# SchematicOscillator.net
KiCad netlist of a schematic drawn in EAGLE
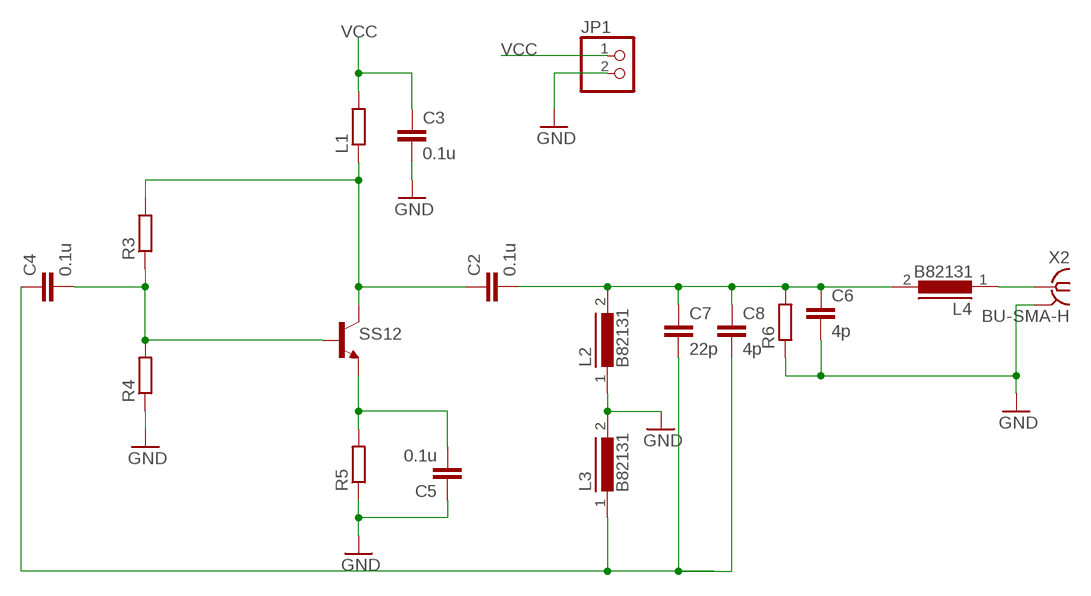
[diagram p0: schematic, sheet 1]

(export (version "E")
  (design (tool "Eeschema 10.0.6"))
  (components
    (comp (ref "C2")
      (value "0.1u")
      (footprint "eagle-import:C0805")
      (libsource (lib "eagle-import") (part "C-EUC0805"))
    )
    (comp (ref "C3")
      (value "0.1u")
      (footprint "eagle-import:C0805")
      (libsource (lib "eagle-import") (part "C-EUC0805"))
    )
    (comp (ref "C4")
      (value "0.1u")
      (footprint "eagle-import:C0805")
      (libsource (lib "eagle-import") (part "C-EUC0805"))
    )
    (comp (ref "C5")
      (value "0.1u")
      (footprint "eagle-import:C0805")
      (libsource (lib "eagle-import") (part "C-EUC0805"))
    )
    (comp (ref "C6")
      (value "4p")
      (footprint "eagle-import:C1206")
      (libsource (lib "eagle-import") (part "C-EUC1206"))
    )
    (comp (ref "C7")
      (value "22p")
      (footprint "eagle-import:C0805")
      (libsource (lib "eagle-import") (part "C-EUC0805"))
    )
    (comp (ref "C8")
      (value "4p")
      (footprint "eagle-import:C1206")
      (libsource (lib "eagle-import") (part "C-EUC1206"))
    )
    (comp (ref "JP1")
      (value "PINHD-1X2")
      (footprint "eagle-import:1X02")
      (libsource (lib "eagle-import") (part "PINHD-1X2"))
    )
    (comp (ref "L1")
      (value "R-EU_M0805")
      (footprint "eagle-import:M0805")
      (libsource (lib "eagle-import") (part "resistor_R-EU_M0805"))
    )
    (comp (ref "L2")
      (value "B82131")
      (footprint "eagle-import:SUKW1-17")
      (libsource (lib "eagle-import") (part "B82131"))
    )
    (comp (ref "L3")
      (value "B82131")
      (footprint "eagle-import:SUKW1-17")
      (libsource (lib "eagle-import") (part "B82131"))
    )
    (comp (ref "L4")
      (value "B82131")
      (footprint "eagle-import:SUKW1-17")
      (libsource (lib "eagle-import") (part "B82131"))
    )
    (comp (ref "R3")
      (value "R-EU_R1206")
      (footprint "eagle-import:R1206")
      (libsource (lib "eagle-import") (part "R-EU_R1206"))
    )
    (comp (ref "R4")
      (value "R-EU_R1206")
      (footprint "eagle-import:R1206")
      (libsource (lib "eagle-import") (part "R-EU_R1206"))
    )
    (comp (ref "R5")
      (value "R-EU_R1206")
      (footprint "eagle-import:R1206")
      (libsource (lib "eagle-import") (part "R-EU_R1206"))
    )
    (comp (ref "R6")
      (value "R-EU_R1206")
      (footprint "eagle-import:R1206")
      (libsource (lib "eagle-import") (part "R-EU_R1206"))
    )
    (comp (ref "SS12")
      (value "-NPN-TO92")
      (footprint "eagle-import:TO92")
      (libsource (lib "eagle-import") (part "-NPN-TO92"))
    )
    (comp (ref "X2")
      (value "BU-SMA-H")
      (footprint "eagle-import:BU-SMA-H")
      (libsource (lib "eagle-import") (part "BU-SMA-H"))
    )
  )
  (nets
    (net (code "1") (name "/VCC") (class "Default")
      (node (ref "C3") (pin "1") (pinfunction "1_1") (pintype "passive"))
      (node (ref "JP1") (pin "1") (pinfunction "1_1") (pintype "passive"))
      (node (ref "L1") (pin "2") (pinfunction "2_2") (pintype "passive"))
    )
    (net (code "2") (name "GND") (class "Default")
      (node (ref "C3") (pin "2") (pinfunction "2_2") (pintype "passive"))
      (node (ref "C5") (pin "1") (pinfunction "1_1") (pintype "passive"))
      (node (ref "C6") (pin "2") (pinfunction "2_2") (pintype "passive"))
      (node (ref "JP1") (pin "2") (pinfunction "2_2") (pintype "passive"))
      (node (ref "L2") (pin "1") (pinfunction "1_1") (pintype "passive"))
      (node (ref "L3") (pin "2") (pinfunction "2_2") (pintype "passive"))
      (node (ref "R4") (pin "1") (pinfunction "1_1") (pintype "passive"))
      (node (ref "R5") (pin "1") (pinfunction "1_1") (pintype "passive"))
      (node (ref "R6") (pin "1") (pinfunction "1_1") (pintype "passive"))
      (node (ref "X2") (pin "2") (pinfunction "2_2") (pintype "passive"))
      (node (ref "X2") (pin "3") (pinfunction "2_3") (pintype "passive"))
      (node (ref "X2") (pin "4") (pinfunction "2_4") (pintype "passive"))
      (node (ref "X2") (pin "5") (pinfunction "2_5") (pintype "passive"))
    )
    (net (code "3") (name "Net-(C2-Pad2)") (class "Default")
      (node (ref "C2") (pin "2") (pinfunction "2_2") (pintype "passive"))
      (node (ref "C6") (pin "1") (pinfunction "1_1") (pintype "passive"))
      (node (ref "C7") (pin "1") (pinfunction "1_1") (pintype "passive"))
      (node (ref "C8") (pin "1") (pinfunction "1_1") (pintype "passive"))
      (node (ref "L2") (pin "2") (pinfunction "2_2") (pintype "passive"))
      (node (ref "L4") (pin "2") (pinfunction "2_2") (pintype "passive"))
      (node (ref "R6") (pin "2") (pinfunction "2_2") (pintype "passive"))
    )
    (net (code "4") (name "Net-(C4-Pad1)") (class "Default")
      (node (ref "C4") (pin "1") (pinfunction "1_1") (pintype "passive"))
      (node (ref "C7") (pin "2") (pinfunction "2_2") (pintype "passive"))
      (node (ref "C8") (pin "2") (pinfunction "2_2") (pintype "passive"))
      (node (ref "L3") (pin "1") (pinfunction "1_1") (pintype "passive"))
    )
    (net (code "5") (name "Net-(L4-Pad1)") (class "Default")
      (node (ref "L4") (pin "1") (pinfunction "1_1") (pintype "passive"))
      (node (ref "X2") (pin "1") (pinfunction "1_1") (pintype "passive"))
    )
    (net (code "6") (name "Net-(SS12-B)") (class "Default")
      (node (ref "C4") (pin "2") (pinfunction "2_2") (pintype "passive"))
      (node (ref "R3") (pin "1") (pinfunction "1_1") (pintype "passive"))
      (node (ref "R4") (pin "2") (pinfunction "2_2") (pintype "passive"))
      (node (ref "SS12") (pin "2") (pinfunction "B_2") (pintype "passive"))
    )
    (net (code "7") (name "Net-(SS12-C)") (class "Default")
      (node (ref "C2") (pin "1") (pinfunction "1_1") (pintype "passive"))
      (node (ref "L1") (pin "1") (pinfunction "1_1") (pintype "passive"))
      (node (ref "R3") (pin "2") (pinfunction "2_2") (pintype "passive"))
      (node (ref "SS12") (pin "3") (pinfunction "C_3") (pintype "passive"))
    )
    (net (code "8") (name "Net-(SS12-E)") (class "Default")
      (node (ref "C5") (pin "2") (pinfunction "2_2") (pintype "passive"))
      (node (ref "R5") (pin "2") (pinfunction "2_2") (pintype "passive"))
      (node (ref "SS12") (pin "1") (pinfunction "E_1") (pintype "passive"))
    )
  )
)
